# Nixie_v1_HV_Supply.net
KiCad netlist of a schematic drawn in EAGLE
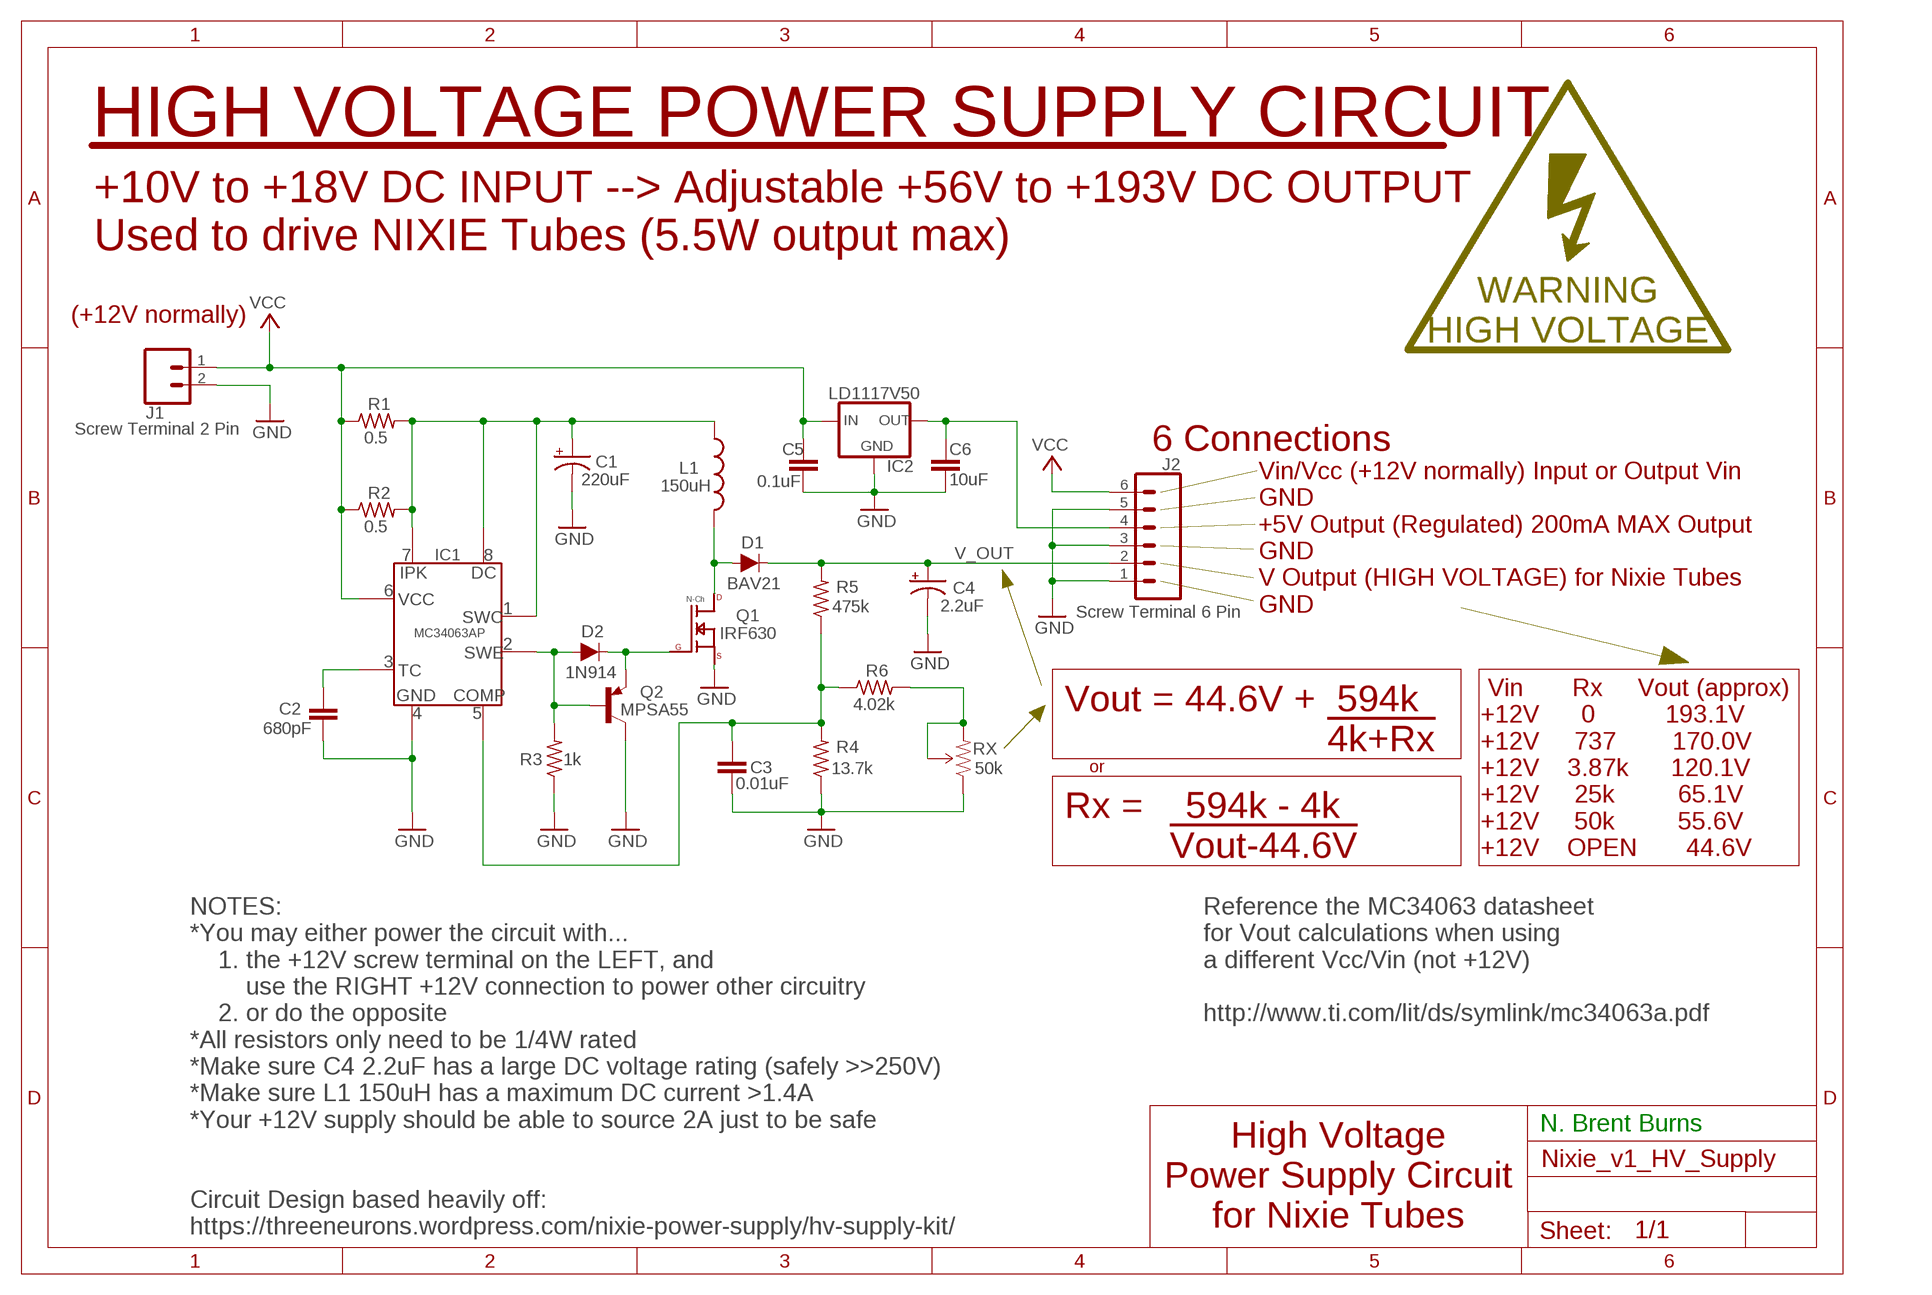
[diagram p0: schematic, sheet 1]

(export (version "E")
  (design (tool "Eeschema 10.0.6"))
  (components
    (comp (ref "C1")
      (value "220uF")
      (footprint "eagle-import:CPOL-RADIAL-5MM-10MM")
      (libsource (lib "eagle-import") (part "1000UF-RADIAL-5MM-25V-20%"))
    )
    (comp (ref "C2")
      (value "680pF")
      (footprint "eagle-import:C2.5-2")
      (libsource (lib "eagle-import") (part "C2.5/2"))
    )
    (comp (ref "C3")
      (value "0.01uF")
      (footprint "eagle-import:C2.5-2")
      (libsource (lib "eagle-import") (part "C2.5/2"))
    )
    (comp (ref "C4")
      (value "2.2uF")
      (footprint "eagle-import:CPOL-RADIAL-2.5MM-6.5MM")
      (libsource (lib "eagle-import") (part "100UF-POLAR-RADIAL-2.5MM-25V-20%"))
    )
    (comp (ref "C5")
      (value "0.1uF")
      (footprint "eagle-import:C2.5-2")
      (libsource (lib "eagle-import") (part "C2.5/2"))
    )
    (comp (ref "C6")
      (value "10uF")
      (footprint "eagle-import:C2.5-2")
      (libsource (lib "eagle-import") (part "C2.5/2"))
    )
    (comp (ref "D1")
      (value "BAV21")
      (footprint "eagle-import:DIODE-1N4148")
      (libsource (lib "eagle-import") (part "DIODE-1N4148"))
    )
    (comp (ref "D2")
      (value "1N914")
      (footprint "eagle-import:DIODE-1N4148")
      (libsource (lib "eagle-import") (part "DIODE-1N4148"))
    )
    (comp (ref "IC1")
      (value "MC34063AP")
      (footprint "eagle-import:DIP08")
      (libsource (lib "eagle-import") (part "MC34063AP"))
    )
    (comp (ref "IC2")
      (value "LD1117V50")
      (footprint "eagle-import:TO220V")
      (libsource (lib "eagle-import") (part "V_REG_LD1117V50"))
    )
    (comp (ref "J1")
      (value "Screw Terminal 2 Pin")
      (footprint "eagle-import:SCREW_TERM_5MM_1X2")
      (libsource (lib "eagle-import") (part "CONNECTOR_2PINSCREW_TERMINAL_5MMPITCH_1X2"))
    )
    (comp (ref "J2")
      (value "Screw Terminal 6 Pin")
      (footprint "eagle-import:SCREW_TERM_5MM_1X6")
      (libsource (lib "eagle-import") (part "CONNECTOR_6PINSCREW_TERMINAL_5MM_PITCH"))
    )
    (comp (ref "L1")
      (value "150uH")
      (footprint "eagle-import:INDUCTOR_11MM_DIAM_6MM_PITCH")
      (libsource (lib "eagle-import") (part "INDUCTOR_150UH_6100-151K-RC"))
    )
    (comp (ref "Q1")
      (value "IRF630")
      (footprint "eagle-import:TO220V")
      (libsource (lib "eagle-import") (part "IRF630"))
    )
    (comp (ref "Q2")
      (value "MPSA55")
      (footprint "eagle-import:TO92-")
      (libsource (lib "eagle-import") (part "MPSA55"))
    )
    (comp (ref "R1")
      (value "0.5")
      (footprint "eagle-import:0204_7")
      (libsource (lib "eagle-import") (part "R-US_0204/7"))
    )
    (comp (ref "R2")
      (value "0.5")
      (footprint "eagle-import:0204_7")
      (libsource (lib "eagle-import") (part "R-US_0204/7"))
    )
    (comp (ref "R3")
      (value "1k")
      (footprint "eagle-import:0204_7")
      (libsource (lib "eagle-import") (part "R-US_0204/7"))
    )
    (comp (ref "R4")
      (value "13.7k")
      (footprint "eagle-import:0204_7")
      (libsource (lib "eagle-import") (part "R-US_0204/7"))
    )
    (comp (ref "R5")
      (value "475k")
      (footprint "eagle-import:0204_7")
      (libsource (lib "eagle-import") (part "R-US_0204/7"))
    )
    (comp (ref "R6")
      (value "4.02k")
      (footprint "eagle-import:0204_7")
      (libsource (lib "eagle-import") (part "R-US_0204/7"))
    )
    (comp (ref "RX")
      (value "50k")
      (footprint "eagle-import:TRIM_POT_PTH")
      (libsource (lib "eagle-import") (part "TRIMPOT"))
    )
  )
  (nets
    (net (code "1") (name "GND") (class "Default")
      (node (ref "C1") (pin "-") (pinfunction "-_-") (pintype "passive"))
      (node (ref "C2") (pin "2") (pinfunction "2_2") (pintype "passive"))
      (node (ref "C3") (pin "2") (pinfunction "2_2") (pintype "passive"))
      (node (ref "C4") (pin "2") (pinfunction "-_2") (pintype "passive"))
      (node (ref "C5") (pin "2") (pinfunction "2_2") (pintype "passive"))
      (node (ref "C6") (pin "2") (pinfunction "2_2") (pintype "passive"))
      (node (ref "IC1") (pin "4") (pinfunction "GND_4") (pintype "power_in"))
      (node (ref "IC2") (pin "1") (pinfunction "GND_1") (pintype "input"))
      (node (ref "J1") (pin "2") (pinfunction "2_2") (pintype "passive"))
      (node (ref "J2") (pin "1") (pinfunction "1_1") (pintype "passive"))
      (node (ref "J2") (pin "3") (pinfunction "3_3") (pintype "passive"))
      (node (ref "J2") (pin "5") (pinfunction "5_5") (pintype "passive"))
      (node (ref "Q1") (pin "3") (pinfunction "SOURCE_3") (pintype "bidirectional"))
      (node (ref "Q2") (pin "3") (pinfunction "C_3") (pintype "passive"))
      (node (ref "R3") (pin "1") (pinfunction "1_1") (pintype "passive"))
      (node (ref "R4") (pin "1") (pinfunction "1_1") (pintype "passive"))
      (node (ref "RX") (pin "1") (pinfunction "CCW_1") (pintype "passive"))
    )
    (net (code "2") (name "Net-(C4-+)") (class "Default")
      (node (ref "C4") (pin "1") (pinfunction "+_1") (pintype "passive"))
      (node (ref "D1") (pin "C") (pinfunction "C_C") (pintype "passive"))
      (node (ref "J2") (pin "2") (pinfunction "2_2") (pintype "passive"))
      (node (ref "R5") (pin "2") (pinfunction "2_2") (pintype "passive"))
    )
    (net (code "3") (name "Net-(IC1-COMP)") (class "Default")
      (node (ref "C3") (pin "1") (pinfunction "1_1") (pintype "passive"))
      (node (ref "IC1") (pin "5") (pinfunction "COMP_5") (pintype "input"))
      (node (ref "R4") (pin "2") (pinfunction "2_2") (pintype "passive"))
      (node (ref "R5") (pin "1") (pinfunction "1_1") (pintype "passive"))
      (node (ref "R6") (pin "1") (pinfunction "1_1") (pintype "passive"))
    )
    (net (code "4") (name "Net-(IC1-DC)") (class "Default")
      (node (ref "C1") (pin "+") (pinfunction "+_+") (pintype "passive"))
      (node (ref "IC1") (pin "1") (pinfunction "SWC_1") (pintype "input"))
      (node (ref "IC1") (pin "7") (pinfunction "IPK_7") (pintype "bidirectional"))
      (node (ref "IC1") (pin "8") (pinfunction "DC_8") (pintype "input"))
      (node (ref "L1") (pin "1") (pinfunction "1_1") (pintype "passive"))
      (node (ref "R1") (pin "2") (pinfunction "2_2") (pintype "passive"))
      (node (ref "R2") (pin "2") (pinfunction "2_2") (pintype "passive"))
    )
    (net (code "5") (name "Net-(IC1-SWE)") (class "Default")
      (node (ref "D2") (pin "A") (pinfunction "A_A") (pintype "passive"))
      (node (ref "IC1") (pin "2") (pinfunction "SWE_2") (pintype "input"))
      (node (ref "Q2") (pin "2") (pinfunction "B_2") (pintype "passive"))
      (node (ref "R3") (pin "2") (pinfunction "2_2") (pintype "passive"))
    )
    (net (code "6") (name "Net-(IC1-TC)") (class "Default")
      (node (ref "C2") (pin "1") (pinfunction "1_1") (pintype "passive"))
      (node (ref "IC1") (pin "3") (pinfunction "TC_3") (pintype "input"))
    )
    (net (code "7") (name "Net-(IC2-OUT)") (class "Default")
      (node (ref "C6") (pin "1") (pinfunction "1_1") (pintype "passive"))
      (node (ref "IC2") (pin "2") (pinfunction "OUT_2") (pintype "passive"))
      (node (ref "J2") (pin "4") (pinfunction "4_4") (pintype "passive"))
    )
    (net (code "8") (name "Net-(Q1-DRAIN)") (class "Default")
      (node (ref "D1") (pin "A") (pinfunction "A_A") (pintype "passive"))
      (node (ref "L1") (pin "2") (pinfunction "2_2") (pintype "passive"))
      (node (ref "Q1") (pin "2") (pinfunction "DRAIN_2") (pintype "bidirectional"))
    )
    (net (code "9") (name "Net-(Q1-GATE)") (class "Default")
      (node (ref "D2") (pin "C") (pinfunction "C_C") (pintype "passive"))
      (node (ref "Q1") (pin "1") (pinfunction "GATE_1") (pintype "bidirectional"))
      (node (ref "Q2") (pin "1") (pinfunction "E_1") (pintype "passive"))
    )
    (net (code "10") (name "Net-(RX-CW)") (class "Default")
      (node (ref "R6") (pin "2") (pinfunction "2_2") (pintype "passive"))
      (node (ref "RX") (pin "2") (pinfunction "WIPER_2") (pintype "passive"))
      (node (ref "RX") (pin "3") (pinfunction "CW_3") (pintype "passive"))
    )
    (net (code "11") (name "VCC") (class "Default")
      (node (ref "C5") (pin "1") (pinfunction "1_1") (pintype "passive"))
      (node (ref "IC1") (pin "6") (pinfunction "VCC_6") (pintype "power_in"))
      (node (ref "IC2") (pin "3") (pinfunction "IN_3") (pintype "input"))
      (node (ref "J1") (pin "1") (pinfunction "1_1") (pintype "passive"))
      (node (ref "J2") (pin "6") (pinfunction "6_6") (pintype "passive"))
      (node (ref "R1") (pin "1") (pinfunction "1_1") (pintype "passive"))
      (node (ref "R2") (pin "1") (pinfunction "1_1") (pintype "passive"))
    )
  )
)
